# main.net
KiCad netlist of a schematic drawn in Altium Designer
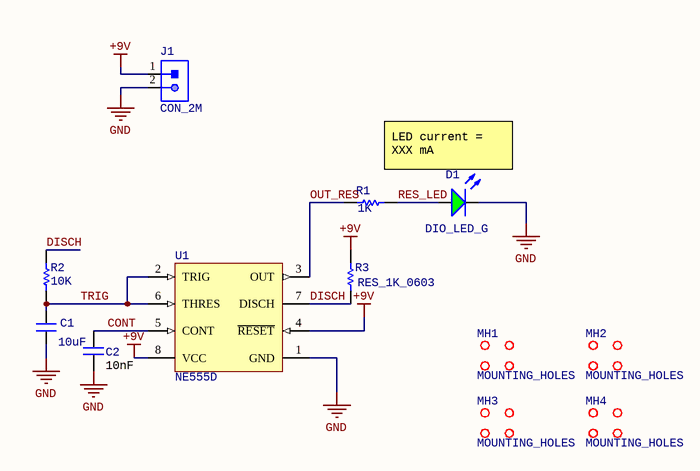
[diagram p0: main.SchDoc]

(export (version "E")
  (design (tool "Eeschema 10.0.6"))
  (components
    (comp (ref "C1")
      (value "10uF")
      (footprint "CAPC0603(1608)55_N")
      (description "CAP CER 10UF 10V X5R 0603")
      (fields (field (name "MPN") "CC0603MRX5R6BB106") (field (name "MANUFACTURER") "Yageo"))
      (libsource (lib "UWRT_Schematic_Library_2020") (part "CAP_10uF_0603"))
    )
    (comp (ref "C2")
      (value "10nF")
      (footprint "CAPC0603(1608)55_N")
      (description "CAP CER 10000PF 16V X7R 0603")
      (fields (field (name "MPN") "CC0603KRX7R7BB103") (field (name "MANUFACTURER") "Yageo"))
      (libsource (lib "UWRT_Schematic_Library_2020") (part "CAP_10nF_0603"))
    )
    (comp (ref "D1")
      (value "DIO_LED_G")
      (footprint "LED_0805_LINE")
      (description "LED GREEN DIFFUSED 0805 SMD")
      (fields (field (name "MPN") "LG R971-KN-1") (field (name "MANUFACTURER") "OSRAM"))
      (libsource (lib "UWRT_Schematic_Library_2020") (part "DIO_LED_G"))
    )
    (comp (ref "J1")
      (value "CON_2M")
      (footprint "JST-B2B-PHSK")
      (libsource (lib "UWRT_Schematic_Library_2020") (part "CON_2M"))
    )
    (comp (ref "MH1")
      (value "MOUNTING_HOLES")
      (footprint "MOUNTING_HOLE")
      (description "6cm x 6cm")
      (libsource (lib "UWRT_Schematic_Library_2020") (part "MOUNTING_HOLES"))
    )
    (comp (ref "MH2")
      (value "MOUNTING_HOLES")
      (footprint "MOUNTING_HOLE")
      (description "6cm x 6cm")
      (libsource (lib "UWRT_Schematic_Library_2020") (part "MOUNTING_HOLES"))
    )
    (comp (ref "MH3")
      (value "MOUNTING_HOLES")
      (footprint "MOUNTING_HOLE")
      (description "6cm x 6cm")
      (libsource (lib "UWRT_Schematic_Library_2020") (part "MOUNTING_HOLES"))
    )
    (comp (ref "MH4")
      (value "MOUNTING_HOLES")
      (footprint "MOUNTING_HOLE")
      (description "6cm x 6cm")
      (libsource (lib "UWRT_Schematic_Library_2020") (part "MOUNTING_HOLES"))
    )
    (comp (ref "R1")
      (value "1K")
      (footprint "RESC0603(1608)_N")
      (description "RES SMD 1K OHM 5% 1/10W 0603")
      (fields (field (name "TOLERANCE") "5%") (field (name "MANUFACTURER") "Yageo"))
      (libsource (lib "UWRT_Schematic_Library_2020") (part "RES_1K_0603"))
    )
    (comp (ref "R2")
      (value "10K")
      (footprint "RESC0603(1608)_N")
      (description "RES SMD 10K OHM 5% 1/10W 0603")
      (fields (field (name "MANUFACTURER") "Yageo") (field (name "MPN") "RC0603JR-0710KL"))
      (libsource (lib "UWRT_Schematic_Library_2020") (part "RES_10K_0603"))
    )
    (comp (ref "R3")
      (value "RES_1K_0603")
      (footprint "RESC0603(1608)_N")
      (description "RES SMD 1K OHM 5% 1/10W 0603")
      (fields (field (name "TOLERANCE") "5%") (field (name "MANUFACTURER") "Yageo"))
      (libsource (lib "UWRT_Schematic_Library_2020") (part "RES_1K_0603"))
    )
    (comp (ref "U1")
      (value "NE555D")
      (footprint "8-SOIC_M")
      (description "Precision Timer, 4.5 to 16 V, 0 to 70 degC, 8-Pin SOIC (D), Green (RoHS & no Sb/Br), Tube")
      (fields (field (name "PARTNUMBER") "NE555") (field (name "MANUFACTURER") "Texas Instruments"))
      (libsource (lib "UWRT_Schematic_Library_2020") (part "NE555D"))
    )
  )
  (nets
    (net (code "1") (name "+9V") (class "Default")
      (node (ref "J1") (pin "1") (pinfunction "1_1") (pintype "passive"))
      (node (ref "R3") (pin "2") (pinfunction "2_2") (pintype "passive"))
      (node (ref "U1") (pin "4") (pinfunction "~{RESET}_4") (pintype "input"))
      (node (ref "U1") (pin "8") (pinfunction "VCC_8") (pintype "power_in"))
    )
    (net (code "2") (name "/CONT") (class "Default")
      (node (ref "C2") (pin "2") (pinfunction "2_2") (pintype "passive"))
      (node (ref "U1") (pin "5") (pinfunction "CONT_5") (pintype "input"))
    )
    (net (code "3") (name "/DISCH") (class "Default")
      (node (ref "R2") (pin "2") (pinfunction "2_2") (pintype "passive"))
      (node (ref "R3") (pin "1") (pinfunction "1_1") (pintype "passive"))
      (node (ref "U1") (pin "7") (pinfunction "DISCH_7") (pintype "open_collector"))
    )
    (net (code "4") (name "/OUT_RES") (class "Default")
      (node (ref "R1") (pin "1") (pinfunction "1_1") (pintype "passive"))
      (node (ref "U1") (pin "3") (pinfunction "OUT_3") (pintype "output"))
    )
    (net (code "5") (name "/RES_LED") (class "Default")
      (node (ref "D1") (pin "1") (pinfunction "A_1") (pintype "passive"))
      (node (ref "R1") (pin "2") (pinfunction "2_2") (pintype "passive"))
    )
    (net (code "6") (name "/TRIG") (class "Default")
      (node (ref "C1") (pin "2") (pinfunction "2_2") (pintype "passive"))
      (node (ref "R2") (pin "1") (pinfunction "1_1") (pintype "passive"))
      (node (ref "U1") (pin "2") (pinfunction "TRIG_2") (pintype "input"))
      (node (ref "U1") (pin "6") (pinfunction "THRES_6") (pintype "input"))
    )
    (net (code "7") (name "GND") (class "Default")
      (node (ref "C1") (pin "1") (pinfunction "1_1") (pintype "passive"))
      (node (ref "C2") (pin "1") (pinfunction "1_1") (pintype "passive"))
      (node (ref "D1") (pin "2") (pinfunction "K_2") (pintype "passive"))
      (node (ref "J1") (pin "2") (pinfunction "2_2") (pintype "passive"))
      (node (ref "U1") (pin "1") (pinfunction "GND_1") (pintype "power_in"))
    )
  )
)
